# Management.net
KiCad netlist of a schematic drawn in Altium Designer
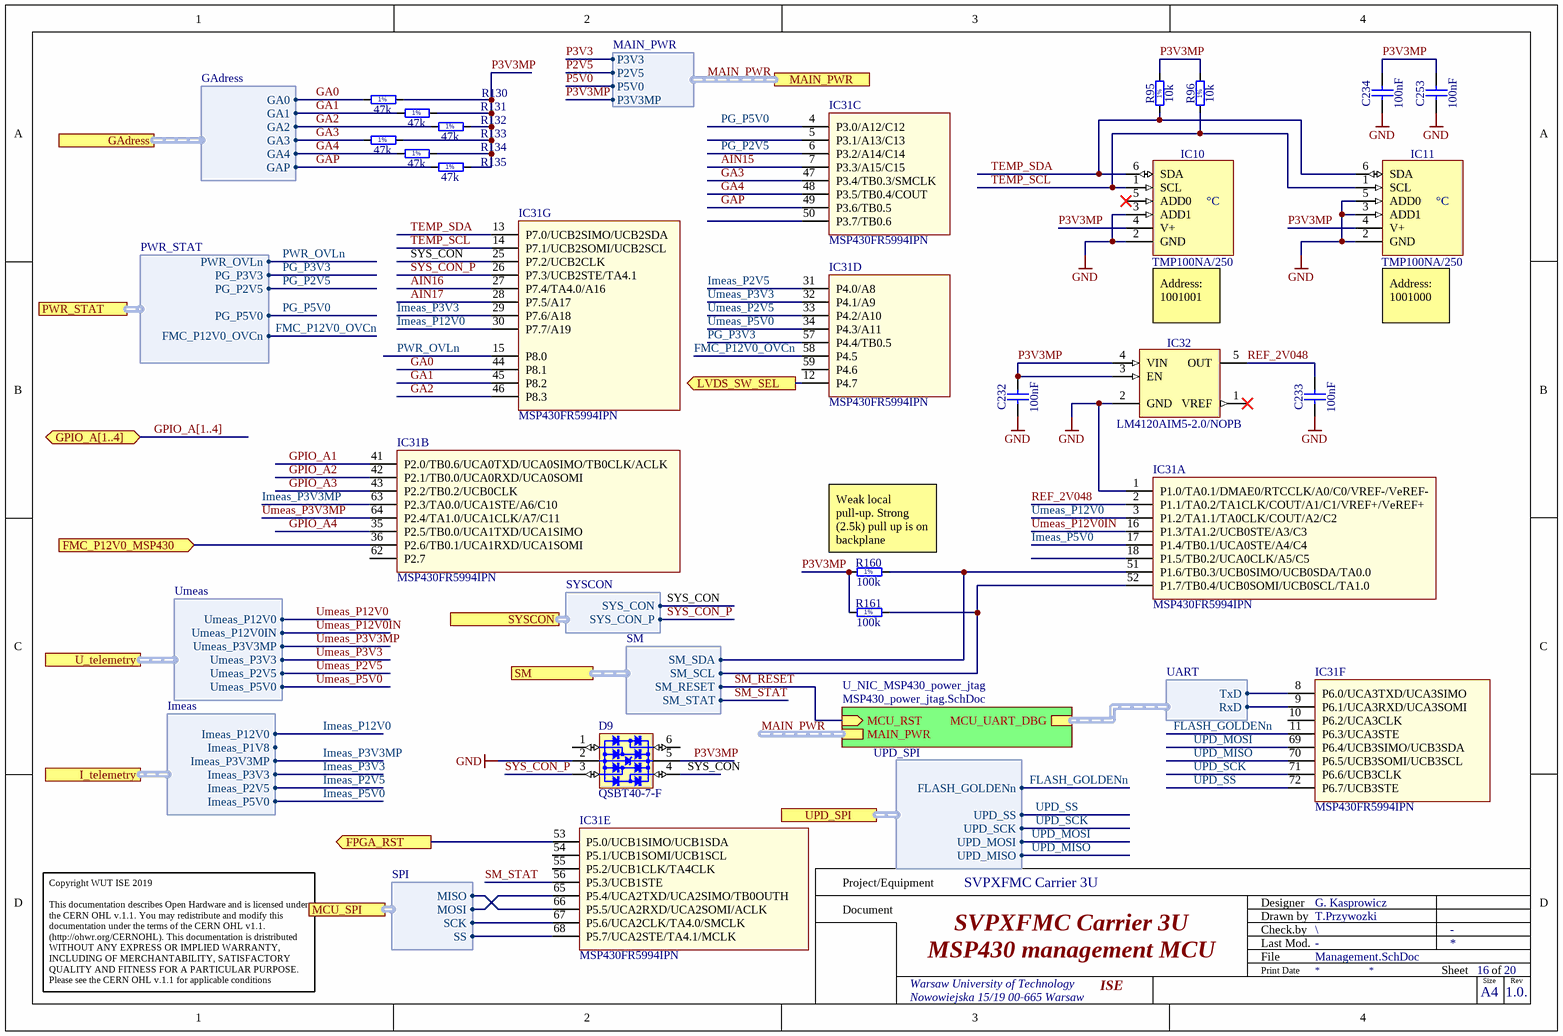
[diagram p0: Management.SchDoc]

(export (version "E")
  (design (tool "Eeschema 10.0.6"))
  (components
    (comp (ref "C232")
      (value "100nF")
      (footprint "CAPC1005X55N")
      (description "Non-polarised capacitor")
      (fields
        (field (name "PART NUMBER") "CC0402_100NF_25V_10%_X7R_YUDEN_TMK105B7104KVHF")
        (field (name "VOLTAGE") "25V")
        (field (name "AUTHOR") "CERN DEM JLC")
      )
      (libsource (lib "Capacitors") (part "Capacitor - non polarized"))
    )
    (comp (ref "C233")
      (value "100nF")
      (footprint "CAPC1005X55N")
      (description "Non-polarised capacitor")
      (fields
        (field (name "PART NUMBER") "CC0402_100NF_25V_10%_X7R_YUDEN_TMK105B7104KVHF")
        (field (name "VOLTAGE") "25V")
        (field (name "AUTHOR") "CERN DEM JLC")
      )
      (libsource (lib "Capacitors") (part "Capacitor - non polarized"))
    )
    (comp (ref "C234")
      (value "100nF")
      (footprint "CAPC1005X55N")
      (description "Non-polarised capacitor")
      (fields
        (field (name "PART NUMBER") "CC0402_100NF_25V_10%_X7R_YUDEN_TMK105B7104KVHF")
        (field (name "VOLTAGE") "25V")
        (field (name "AUTHOR") "CERN DEM JLC")
      )
      (libsource (lib "Capacitors") (part "Capacitor - non polarized"))
    )
    (comp (ref "C253")
      (value "100nF")
      (footprint "CAPC1005X55N")
      (description "Non-polarised capacitor")
      (fields
        (field (name "PART NUMBER") "CC0402_100NF_25V_10%_X7R_YUDEN_TMK105B7104KVHF")
        (field (name "VOLTAGE") "25V")
        (field (name "AUTHOR") "CERN DEM JLC")
      )
      (libsource (lib "Capacitors") (part "Capacitor - non polarized"))
    )
    (comp (ref "D9")
      (value "QSBT40-7-F")
      (footprint "SOT65P210X110-6N")
      (libsource (lib "LIBRARY_SCH") (part "D_TVS_QSBT40-7-F"))
    )
    (comp (ref "IC10")
      (value "TMP100NA/250")
      (footprint "SOT95P280X145-6N")
      (description "Digital Temperature Sensor with I2C Interface")
      (fields (field (name "MANUFACTURER") "TEXAS INSTRUMENTS") (field (name "AUTHOR") "CERN DEM JLC"))
      (libsource (lib "ICs And Semiconductors") (part "TMP100"))
    )
    (comp (ref "IC11")
      (value "TMP100NA/250")
      (footprint "SOT95P280X145-6N")
      (description "Digital Temperature Sensor with I2C Interface")
      (fields (field (name "MANUFACTURER") "TEXAS INSTRUMENTS") (field (name "AUTHOR") "CERN DEM JLC"))
      (libsource (lib "ICs And Semiconductors") (part "TMP100"))
    )
    (comp (ref "IC31")
      (value "MSP430FR5994IPN")
      (footprint "QFP50P1400X1400X120-80N")
      (fields (field (name "MANUFACTURER") "TI"))
      (libsource (lib "ICs_And_Semiconductors") (part "MSP430FR5994IPN"))
    )
    (comp (ref "IC32")
      (value "LM4120AIM5-2.0/NOPB")
      (footprint "SOT95P280X145-5N")
      (description "Precision Micropower Low Dropout Voltage Reference")
      (fields (field (name "MANUFACTURER") "TEXAS INSTRUMENTS") (field (name "AUTHOR") "CERN DEM JMW"))
      (libsource (lib "ICs And Semiconductors") (part "LM4120"))
    )
    (comp (ref "R95")
      (value "10k")
      (footprint "RESC1005X40N")
      (description "Resistor - 1%")
      (fields
        (field (name "PART NUMBER") "R0402_10K_1%_0.0625W_100PPM")
        (field (name "POWER") "0.0625W")
        (field (name "AUTHOR") "CERN DEM JLC")
      )
      (libsource (lib "Resistors") (part "Resistor - 1%"))
    )
    (comp (ref "R96")
      (value "10k")
      (footprint "RESC1005X40N")
      (description "Resistor - 1%")
      (fields
        (field (name "PART NUMBER") "R0402_10K_1%_0.0625W_100PPM")
        (field (name "POWER") "0.0625W")
        (field (name "AUTHOR") "CERN DEM JLC")
      )
      (libsource (lib "Resistors") (part "Resistor - 1%"))
    )
    (comp (ref "R130")
      (value "47k")
      (footprint "RESC1005X40N")
      (description "Resistor - 1%")
      (fields
        (field (name "PART NUMBER") "R0402_47K_1%_0.0625W_100PPM")
        (field (name "POWER") "0.0625W")
        (field (name "AUTHOR") "CERN DEM JLC")
      )
      (libsource (lib "Resistors") (part "Resistor - 1%"))
    )
    (comp (ref "R131")
      (value "47k")
      (footprint "RESC1005X40N")
      (description "Resistor - 1%")
      (fields
        (field (name "PART NUMBER") "R0402_47K_1%_0.0625W_100PPM")
        (field (name "POWER") "0.0625W")
        (field (name "AUTHOR") "CERN DEM JLC")
      )
      (libsource (lib "Resistors") (part "Resistor - 1%"))
    )
    (comp (ref "R132")
      (value "47k")
      (footprint "RESC1005X40N")
      (description "Resistor - 1%")
      (fields
        (field (name "PART NUMBER") "R0402_47K_1%_0.0625W_100PPM")
        (field (name "POWER") "0.0625W")
        (field (name "AUTHOR") "CERN DEM JLC")
      )
      (libsource (lib "Resistors") (part "Resistor - 1%"))
    )
    (comp (ref "R133")
      (value "47k")
      (footprint "RESC1005X40N")
      (description "Resistor - 1%")
      (fields
        (field (name "PART NUMBER") "R0402_47K_1%_0.0625W_100PPM")
        (field (name "POWER") "0.0625W")
        (field (name "AUTHOR") "CERN DEM JLC")
      )
      (libsource (lib "Resistors") (part "Resistor - 1%"))
    )
    (comp (ref "R134")
      (value "47k")
      (footprint "RESC1005X40N")
      (description "Resistor - 1%")
      (fields
        (field (name "PART NUMBER") "R0402_47K_1%_0.0625W_100PPM")
        (field (name "POWER") "0.0625W")
        (field (name "AUTHOR") "CERN DEM JLC")
      )
      (libsource (lib "Resistors") (part "Resistor - 1%"))
    )
    (comp (ref "R135")
      (value "47k")
      (footprint "RESC1005X40N")
      (description "Resistor - 1%")
      (fields
        (field (name "PART NUMBER") "R0402_47K_1%_0.0625W_100PPM")
        (field (name "POWER") "0.0625W")
        (field (name "AUTHOR") "CERN DEM JLC")
      )
      (libsource (lib "Resistors") (part "Resistor - 1%"))
    )
    (comp (ref "R160")
      (value "100k")
      (footprint "RESC1005X40N")
      (description "Resistor - 1%")
      (fields
        (field (name "PART NUMBER") "R0402_100K_1%_0.0625W_100PPM")
        (field (name "POWER") "0.0625W")
        (field (name "AUTHOR") "CERN DEM JLC")
      )
      (libsource (lib "Resistors") (part "Resistor - 1%"))
    )
    (comp (ref "R161")
      (value "100k")
      (footprint "RESC1005X40N")
      (description "Resistor - 1%")
      (fields
        (field (name "PART NUMBER") "R0402_100K_1%_0.0625W_100PPM")
        (field (name "POWER") "0.0625W")
        (field (name "AUTHOR") "CERN DEM JLC")
      )
      (libsource (lib "Resistors") (part "Resistor - 1%"))
    )
  )
  (nets
    (net (code "12") (name "/AIN15") (class "Default")
      (node (ref "IC31") (pin "7") (pinfunction "P3.3/A15/C15_7") (pintype "passive"))
    )
    (net (code "13") (name "/AIN16") (class "Default")
      (node (ref "IC31") (pin "27") (pinfunction "P7.4/TA4.0/A16_27") (pintype "passive"))
    )
    (net (code "14") (name "/AIN17") (class "Default")
      (node (ref "IC31") (pin "28") (pinfunction "P7.5/A17_28") (pintype "passive"))
    )
    (net (code "15") (name "/FLASH_GOLDENn") (class "Default")
      (node (ref "IC31") (pin "11") (pinfunction "P6.3/UCA3STE_11") (pintype "passive"))
    )
    (net (code "16") (name "/FMC_P12V0_MSP430") (class "Default")
      (node (ref "IC31") (pin "36") (pinfunction "P2.6/TB0.1/UCA1RXD/UCA1SOMI_36") (pintype "passive"))
    )
    (net (code "17") (name "/FMC_P12V0_OVCn") (class "Default")
      (node (ref "IC31") (pin "58") (pinfunction "P4.5_58") (pintype "passive"))
    )
    (net (code "18") (name "/FPGA_RST") (class "Default")
      (node (ref "IC31") (pin "53") (pinfunction "P5.0/UCB1SIMO/UCB1SDA_53") (pintype "passive"))
    )
    (net (code "19") (name "/GA0") (class "Default")
      (node (ref "IC31") (pin "44") (pinfunction "P8.1_44") (pintype "passive"))
      (node (ref "R130") (pin "1") (pinfunction "1_1") (pintype "passive"))
    )
    (net (code "20") (name "/GA1") (class "Default")
      (node (ref "IC31") (pin "45") (pinfunction "P8.2_45") (pintype "passive"))
      (node (ref "R131") (pin "1") (pinfunction "1_1") (pintype "passive"))
    )
    (net (code "21") (name "/GA2") (class "Default")
      (node (ref "IC31") (pin "46") (pinfunction "P8.3_46") (pintype "passive"))
      (node (ref "R132") (pin "1") (pinfunction "1_1") (pintype "passive"))
    )
    (net (code "22") (name "/GA3") (class "Default")
      (node (ref "IC31") (pin "47") (pinfunction "P3.4/TB0.3/SMCLK_47") (pintype "passive"))
      (node (ref "R133") (pin "1") (pinfunction "1_1") (pintype "passive"))
    )
    (net (code "23") (name "/GA4") (class "Default")
      (node (ref "IC31") (pin "48") (pinfunction "P3.5/TB0.4/COUT_48") (pintype "passive"))
      (node (ref "R134") (pin "1") (pinfunction "1_1") (pintype "passive"))
    )
    (net (code "24") (name "/GAP") (class "Default")
      (node (ref "IC31") (pin "49") (pinfunction "P3.6/TB0.5_49") (pintype "passive"))
      (node (ref "R135") (pin "1") (pinfunction "1_1") (pintype "passive"))
    )
    (net (code "25") (name "/GPIO_A1") (class "Default")
      (node (ref "IC31") (pin "41") (pinfunction "P2.0/TB0.6/UCA0TXD/UCA0SIMO/TB0CLK/ACLK_41") (pintype "passive"))
    )
    (net (code "26") (name "/GPIO_A2") (class "Default")
      (node (ref "IC31") (pin "42") (pinfunction "P2.1/TB0.0/UCA0RXD/UCA0SOMI_42") (pintype "passive"))
    )
    (net (code "27") (name "/GPIO_A3") (class "Default")
      (node (ref "IC31") (pin "43") (pinfunction "P2.2/TB0.2/UCB0CLK_43") (pintype "passive"))
    )
    (net (code "28") (name "/GPIO_A4") (class "Default")
      (node (ref "IC31") (pin "35") (pinfunction "P2.5/TB0.0/UCA1TXD/UCA1SIMO_35") (pintype "passive"))
    )
    (net (code "30") (name "/Imeas_P2V5") (class "Default")
      (node (ref "IC31") (pin "31") (pinfunction "P4.0/A8_31") (pintype "passive"))
    )
    (net (code "31") (name "/Imeas_P3V3") (class "Default")
      (node (ref "IC31") (pin "29") (pinfunction "P7.6/A18_29") (pintype "passive"))
    )
    (net (code "32") (name "/Imeas_P3V3MP") (class "Default")
      (node (ref "IC31") (pin "63") (pinfunction "P2.3/TA0.0/UCA1STE/A6/C10_63") (pintype "passive"))
    )
    (net (code "33") (name "/Imeas_P5V0") (class "Default")
      (node (ref "IC31") (pin "17") (pinfunction "P1.4/TB0.1/UCA0STE/A4/C4_17") (pintype "passive"))
    )
    (net (code "34") (name "/Imeas_P12V0") (class "Default")
      (node (ref "IC31") (pin "30") (pinfunction "P7.7/A19_30") (pintype "passive"))
    )
    (net (code "35") (name "/LVDS_SW_SEL") (class "Default")
      (node (ref "IC31") (pin "12") (pinfunction "P4.7_12") (pintype "passive"))
    )
    (net (code "37") (name "/MISO") (class "Default")
      (node (ref "IC31") (pin "66") (pinfunction "P5.5/UCA2RXD/UCA2SOMI/ACLK_66") (pintype "passive"))
    )
    (net (code "38") (name "/MOSI") (class "Default")
      (node (ref "IC31") (pin "65") (pinfunction "P5.4/UCA2TXD/UCA2SIMO/TB0OUTH_65") (pintype "passive"))
    )
    (net (code "41") (name "/P3V3MP") (class "Default")
      (node (ref "C232") (pin "2") (pinfunction "2_2") (pintype "passive"))
      (node (ref "C234") (pin "2") (pinfunction "2_2") (pintype "passive"))
      (node (ref "C253") (pin "2") (pinfunction "2_2") (pintype "passive"))
      (node (ref "D9") (pin "5") (pinfunction "VBUS_5") (pintype "power_in"))
      (node (ref "IC10") (pin "4") (pinfunction "V+_4") (pintype "power_in"))
      (node (ref "IC11") (pin "4") (pinfunction "V+_4") (pintype "power_in"))
      (node (ref "IC32") (pin "3") (pinfunction "EN_3") (pintype "input"))
      (node (ref "IC32") (pin "4") (pinfunction "VIN_4") (pintype "input"))
      (node (ref "R130") (pin "2") (pinfunction "2_2") (pintype "passive"))
      (node (ref "R131") (pin "2") (pinfunction "2_2") (pintype "passive"))
      (node (ref "R132") (pin "2") (pinfunction "2_2") (pintype "passive"))
      (node (ref "R133") (pin "2") (pinfunction "2_2") (pintype "passive"))
      (node (ref "R134") (pin "2") (pinfunction "2_2") (pintype "passive"))
      (node (ref "R135") (pin "2") (pinfunction "2_2") (pintype "passive"))
      (node (ref "R160") (pin "1") (pinfunction "1_1") (pintype "passive"))
      (node (ref "R161") (pin "1") (pinfunction "1_1") (pintype "passive"))
      (node (ref "R95") (pin "2") (pinfunction "2_2") (pintype "passive"))
      (node (ref "R96") (pin "2") (pinfunction "2_2") (pintype "passive"))
    )
    (net (code "43") (name "/PG_P2V5") (class "Default")
      (node (ref "IC31") (pin "6") (pinfunction "P3.2/A14/C14_6") (pintype "passive"))
    )
    (net (code "44") (name "/PG_P3V3") (class "Default")
      (node (ref "IC31") (pin "57") (pinfunction "P4.4/TB0.5_57") (pintype "passive"))
    )
    (net (code "45") (name "/PG_P5V0") (class "Default")
      (node (ref "IC31") (pin "4") (pinfunction "P3.0/A12/C12_4") (pintype "passive"))
    )
    (net (code "46") (name "/PWR_OVLn") (class "Default")
      (node (ref "IC31") (pin "15") (pinfunction "P8.0_15") (pintype "passive"))
    )
    (net (code "47") (name "/REF_2V048") (class "Default")
      (node (ref "C233") (pin "2") (pinfunction "2_2") (pintype "passive"))
      (node (ref "IC31") (pin "2") (pinfunction "P1.1/TA0.2/TA1CLK/COUT/A1/C1/VREF+/VeREF+_2") (pintype "passive"))
      (node (ref "IC32") (pin "5") (pinfunction "OUT_5") (pintype "power_in"))
    )
    (net (code "48") (name "/RxD") (class "Default")
      (node (ref "IC31") (pin "9") (pinfunction "P6.1/UCA3RXD/UCA3SOMI_9") (pintype "passive"))
    )
    (net (code "49") (name "/SCK") (class "Default")
      (node (ref "IC31") (pin "67") (pinfunction "P5.6/UCA2CLK/TA4.0/SMCLK_67") (pintype "passive"))
    )
    (net (code "51") (name "/SM_SCL") (class "Default")
      (node (ref "IC31") (pin "52") (pinfunction "P1.7/TB0.4/UCB0SOMI/UCB0SCL/TA1.0_52") (pintype "passive"))
      (node (ref "R161") (pin "2") (pinfunction "2_2") (pintype "passive"))
    )
    (net (code "52") (name "/SM_SDA") (class "Default")
      (node (ref "IC31") (pin "51") (pinfunction "P1.6/TB0.3/UCB0SIMO/UCB0SDA/TA0.0_51") (pintype "passive"))
      (node (ref "R160") (pin "2") (pinfunction "2_2") (pintype "passive"))
    )
    (net (code "53") (name "/SM_STAT") (class "Default")
      (node (ref "IC31") (pin "56") (pinfunction "P5.3/UCB1STE_56") (pintype "passive"))
    )
    (net (code "54") (name "/SS") (class "Default")
      (node (ref "IC31") (pin "68") (pinfunction "P5.7/UCA2STE/TA4.1/MCLK_68") (pintype "passive"))
    )
    (net (code "55") (name "/SYS_CON") (class "Default")
      (node (ref "D9") (pin "4") (pinfunction "I/O3_4") (pintype "bidirectional"))
      (node (ref "IC31") (pin "25") (pinfunction "P7.2/UCB2CLK_25") (pintype "passive"))
    )
    (net (code "56") (name "/SYS_CON_P") (class "Default")
      (node (ref "D9") (pin "3") (pinfunction "I/O2_3") (pintype "bidirectional"))
      (node (ref "IC31") (pin "26") (pinfunction "P7.3/UCB2STE/TA4.1_26") (pintype "passive"))
    )
    (net (code "57") (name "/TEMP_SCL") (class "Default")
      (node (ref "IC10") (pin "1") (pinfunction "SCL_1") (pintype "input"))
      (node (ref "IC11") (pin "1") (pinfunction "SCL_1") (pintype "input"))
      (node (ref "IC31") (pin "14") (pinfunction "P7.1/UCB2SOMI/UCB2SCL_14") (pintype "passive"))
      (node (ref "R96") (pin "1") (pinfunction "1_1") (pintype "passive"))
    )
    (net (code "58") (name "/TEMP_SDA") (class "Default")
      (node (ref "IC10") (pin "6") (pinfunction "SDA_6") (pintype "bidirectional"))
      (node (ref "IC11") (pin "6") (pinfunction "SDA_6") (pintype "bidirectional"))
      (node (ref "IC31") (pin "13") (pinfunction "P7.0/UCB2SIMO/UCB2SDA_13") (pintype "passive"))
      (node (ref "R95") (pin "1") (pinfunction "1_1") (pintype "passive"))
    )
    (net (code "59") (name "/TxD") (class "Default")
      (node (ref "IC31") (pin "8") (pinfunction "P6.0/UCA3TXD/UCA3SIMO_8") (pintype "passive"))
    )
    (net (code "60") (name "/UPD_MISO") (class "Default")
      (node (ref "IC31") (pin "70") (pinfunction "P6.5/UCB3SOMI/UCB3SCL_70") (pintype "passive"))
    )
    (net (code "61") (name "/UPD_MOSI") (class "Default")
      (node (ref "IC31") (pin "69") (pinfunction "P6.4/UCB3SIMO/UCB3SDA_69") (pintype "passive"))
    )
    (net (code "62") (name "/UPD_SCK") (class "Default")
      (node (ref "IC31") (pin "71") (pinfunction "P6.6/UCB3CLK_71") (pintype "passive"))
    )
    (net (code "63") (name "/UPD_SS") (class "Default")
      (node (ref "IC31") (pin "72") (pinfunction "P6.7/UCB3STE_72") (pintype "passive"))
    )
    (net (code "64") (name "/Umeas_P2V5") (class "Default")
      (node (ref "IC31") (pin "33") (pinfunction "P4.2/A10_33") (pintype "passive"))
    )
    (net (code "65") (name "/Umeas_P3V3") (class "Default")
      (node (ref "IC31") (pin "32") (pinfunction "P4.1/A9_32") (pintype "passive"))
    )
    (net (code "66") (name "/Umeas_P3V3MP") (class "Default")
      (node (ref "IC31") (pin "64") (pinfunction "P2.4/TA1.0/UCA1CLK/A7/C11_64") (pintype "passive"))
    )
    (net (code "67") (name "/Umeas_P5V0") (class "Default")
      (node (ref "IC31") (pin "34") (pinfunction "P4.3/A11_34") (pintype "passive"))
    )
    (net (code "68") (name "/Umeas_P12V0") (class "Default")
      (node (ref "IC31") (pin "3") (pinfunction "P1.2/TA1.1/TA0CLK/COUT/A2/C2_3") (pintype "passive"))
    )
    (net (code "69") (name "/Umeas_P12V0IN") (class "Default")
      (node (ref "IC31") (pin "16") (pinfunction "P1.3/TA1.2/UCB0STE/A3/C3_16") (pintype "passive"))
    )
    (net (code "80") (name "GND") (class "Default")
      (node (ref "C232") (pin "1") (pinfunction "1_1") (pintype "passive"))
      (node (ref "C233") (pin "1") (pinfunction "1_1") (pintype "passive"))
      (node (ref "C234") (pin "1") (pinfunction "1_1") (pintype "passive"))
      (node (ref "C253") (pin "1") (pinfunction "1_1") (pintype "passive"))
      (node (ref "D9") (pin "2") (pinfunction "GND_2") (pintype "power_in"))
      (node (ref "IC10") (pin "2") (pinfunction "GND_2") (pintype "power_in"))
      (node (ref "IC10") (pin "3") (pinfunction "ADD1_3") (pintype "input"))
      (node (ref "IC11") (pin "2") (pinfunction "GND_2") (pintype "power_in"))
      (node (ref "IC11") (pin "3") (pinfunction "ADD1_3") (pintype "input"))
      (node (ref "IC11") (pin "5") (pinfunction "ADD0_5") (pintype "input"))
      (node (ref "IC31") (pin "1") (pinfunction "P1.0/TA0.1/DMAE0/RTCCLK/A0/C0/VREF-/VeREF-_1") (pintype "passive"))
      (node (ref "IC32") (pin "2") (pinfunction "GND_2") (pintype "power_in"))
    )
    (net (code "81") (name "unconnected-(D9-I{slash}O1-Pad1)") (class "Default")
      (node (ref "D9") (pin "1") (pinfunction "I/O1_1") (pintype "bidirectional"))
    )
    (net (code "82") (name "unconnected-(D9-I{slash}O4-Pad6)") (class "Default")
      (node (ref "D9") (pin "6") (pinfunction "I/O4_6") (pintype "bidirectional"))
    )
    (net (code "83") (name "unconnected-(IC10-ADD0-Pad5)") (class "Default")
      (node (ref "IC10") (pin "5") (pinfunction "ADD0_5") (pintype "input+no_connect"))
    )
    (net (code "84") (name "unconnected-(IC31A-P1.5{slash}TB0.2{slash}UCA0CLK{slash}A5{slash}C5-Pad18)") (class "Default")
      (node (ref "IC31") (pin "18") (pinfunction "P1.5/TB0.2/UCA0CLK/A5/C5_18") (pintype "passive"))
    )
    (net (code "85") (name "unconnected-(IC31B-P2.7-Pad62)") (class "Default")
      (node (ref "IC31") (pin "62") (pinfunction "P2.7_62") (pintype "passive"))
    )
    (net (code "86") (name "unconnected-(IC31C-P3.1{slash}A13{slash}C13-Pad5)") (class "Default")
      (node (ref "IC31") (pin "5") (pinfunction "P3.1/A13/C13_5") (pintype "passive"))
    )
    (net (code "87") (name "unconnected-(IC31C-P3.7{slash}TB0.6-Pad50)") (class "Default")
      (node (ref "IC31") (pin "50") (pinfunction "P3.7/TB0.6_50") (pintype "passive"))
    )
    (net (code "88") (name "unconnected-(IC31D-P4.6-Pad59)") (class "Default")
      (node (ref "IC31") (pin "59") (pinfunction "P4.6_59") (pintype "passive"))
    )
    (net (code "89") (name "unconnected-(IC31E-P5.1{slash}UCB1SOMI{slash}UCB1SCL-Pad54)") (class "Default")
      (node (ref "IC31") (pin "54") (pinfunction "P5.1/UCB1SOMI/UCB1SCL_54") (pintype "passive"))
    )
    (net (code "90") (name "unconnected-(IC31E-P5.2{slash}UCB1CLK{slash}TA4CLK-Pad55)") (class "Default")
      (node (ref "IC31") (pin "55") (pinfunction "P5.2/UCB1CLK/TA4CLK_55") (pintype "passive"))
    )
    (net (code "91") (name "unconnected-(IC31F-P6.2{slash}UCA3CLK-Pad10)") (class "Default")
      (node (ref "IC31") (pin "10") (pinfunction "P6.2/UCA3CLK_10") (pintype "passive"))
    )
    (net (code "92") (name "unconnected-(IC32-VREF-Pad1)") (class "Default")
      (node (ref "IC32") (pin "1") (pinfunction "VREF_1") (pintype "output+no_connect"))
    )
  )
)
